# silelis_version1.net
KiCad netlist of a schematic drawn in EAGLE
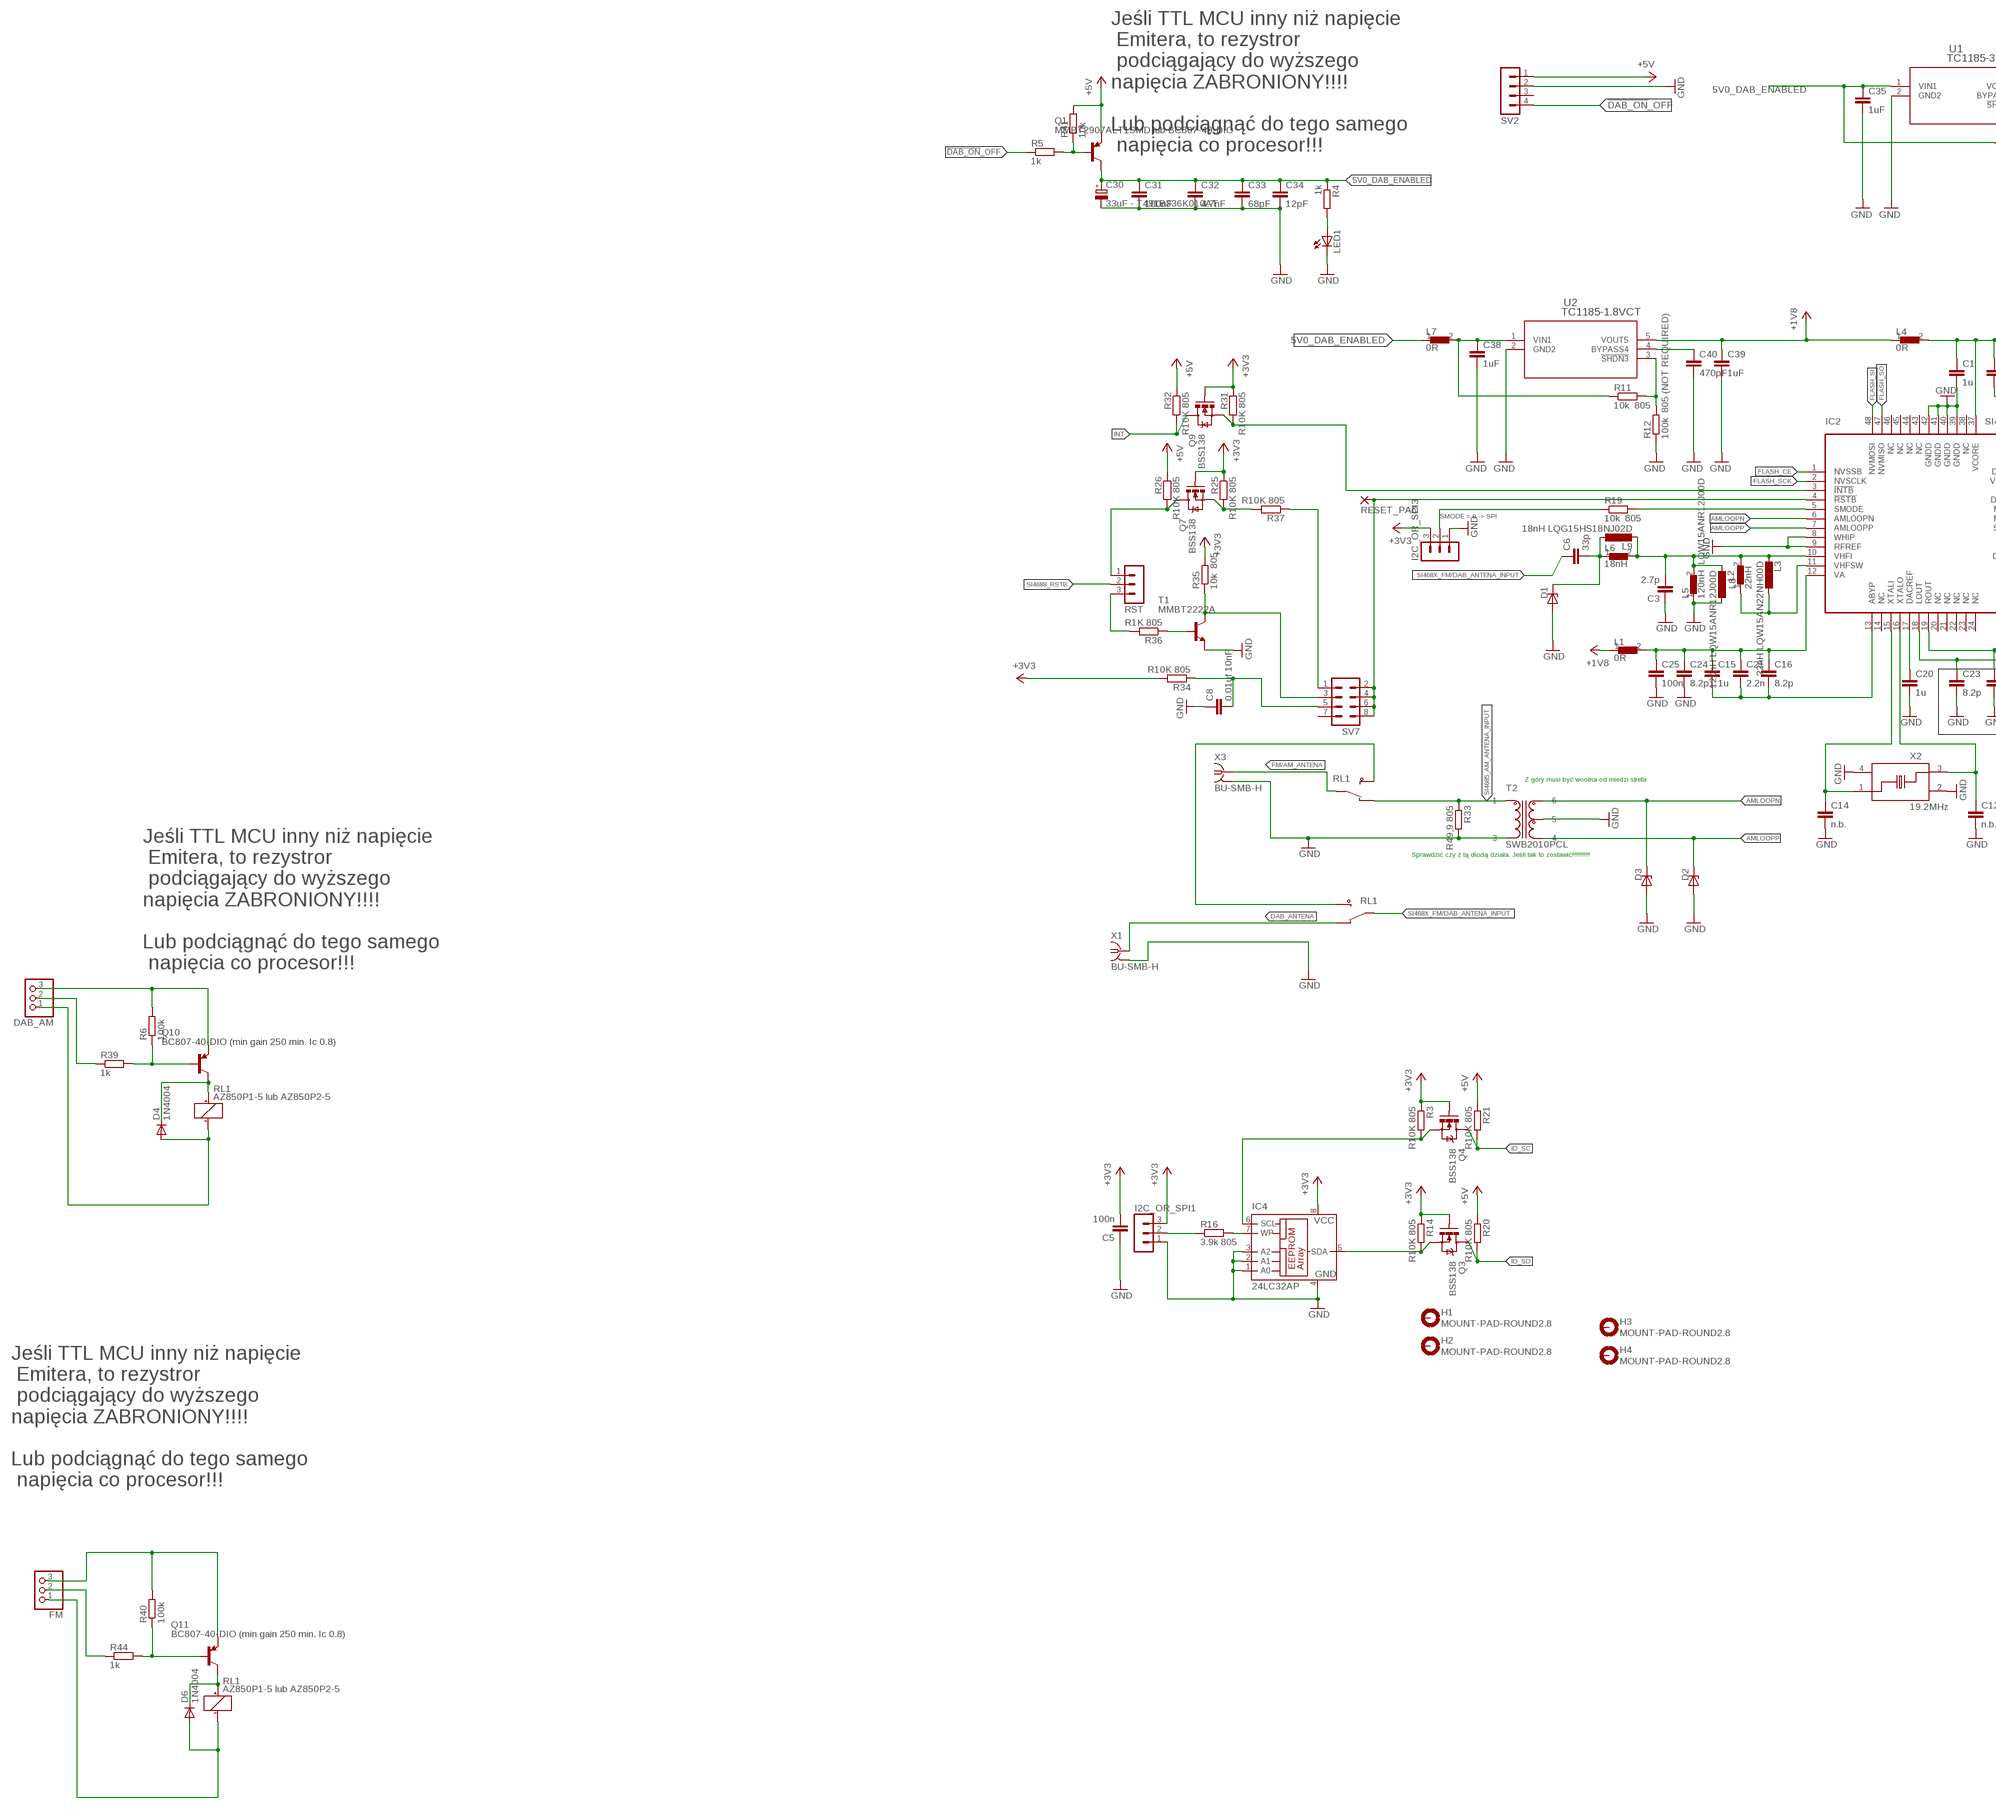
[diagram p0: schematic, sheet 1, part 1 of 2]
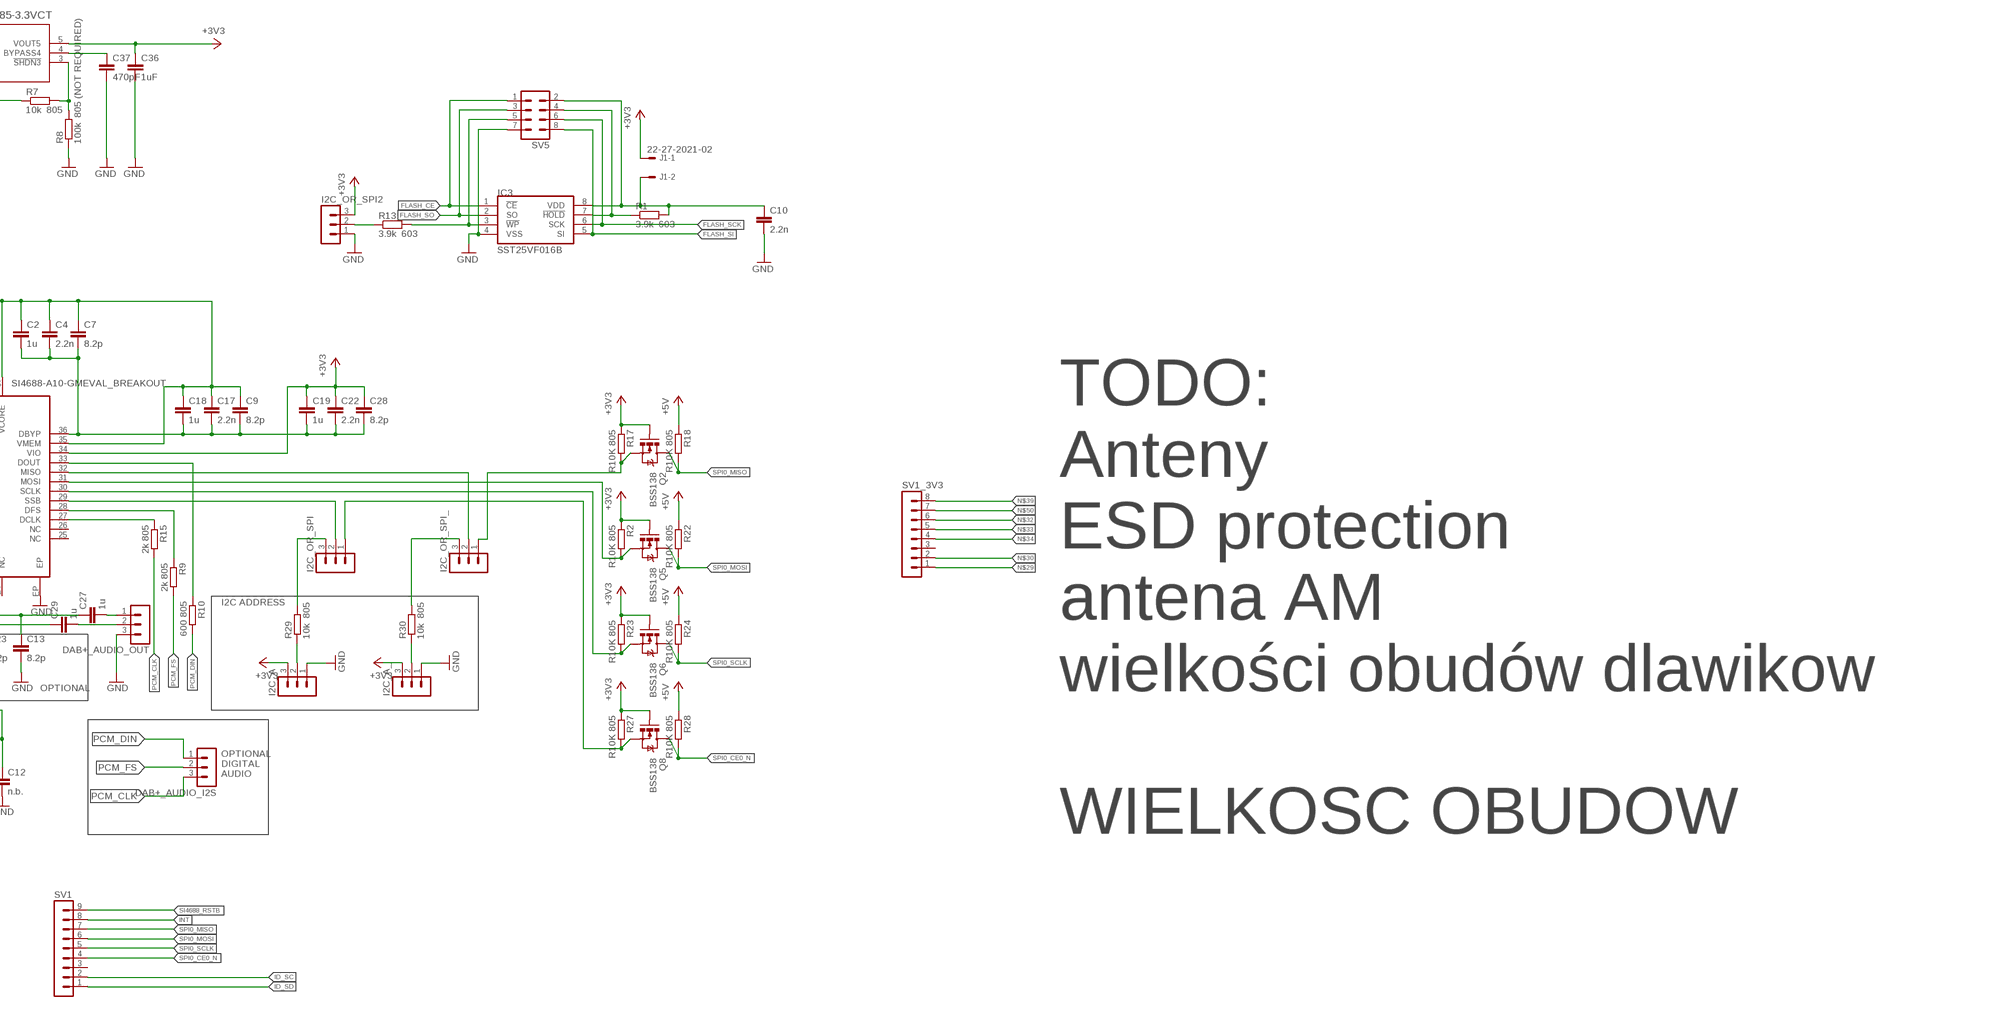
[diagram p1: schematic, sheet 1, part 2 of 2]

(export (version "E")
  (design (tool "Eeschema 10.0.6"))
  (components
    (comp (ref "C1")
      (value "1u")
      (footprint "eagle-import:C0805")
      (libsource (lib "eagle-import") (part "resistor_C-EUC0805"))
    )
    (comp (ref "C2")
      (value "1u")
      (footprint "eagle-import:C0805")
      (libsource (lib "eagle-import") (part "resistor_C-EUC0805"))
    )
    (comp (ref "C3")
      (value "2.7p")
      (footprint "eagle-import:C0603")
      (libsource (lib "eagle-import") (part "resistor_C-EUC0603"))
    )
    (comp (ref "C4")
      (value "2.2n")
      (footprint "eagle-import:C0805")
      (libsource (lib "eagle-import") (part "resistor_C-EUC0805"))
    )
    (comp (ref "C5")
      (value "100n")
      (footprint "eagle-import:C0805")
      (libsource (lib "eagle-import") (part "resistor_C-EUC0805"))
    )
    (comp (ref "C6")
      (value "33p")
      (footprint "eagle-import:C0603")
      (libsource (lib "eagle-import") (part "resistor_C-EUC0603"))
    )
    (comp (ref "C7")
      (value "8.2p")
      (footprint "eagle-import:C0805")
      (libsource (lib "eagle-import") (part "resistor_C-EUC0805"))
    )
    (comp (ref "C8")
      (value "0.01uf 10nF")
      (footprint "eagle-import:C0805")
      (libsource (lib "eagle-import") (part "C-EUC0805"))
    )
    (comp (ref "C9")
      (value "8.2p")
      (footprint "eagle-import:C0805")
      (libsource (lib "eagle-import") (part "resistor_C-EUC0805"))
    )
    (comp (ref "C10")
      (value "2.2n")
      (footprint "eagle-import:C0805")
      (libsource (lib "eagle-import") (part "resistor_C-EUC0805"))
    )
    (comp (ref "C12")
      (value "n.b.")
      (footprint "eagle-import:C0805")
      (libsource (lib "eagle-import") (part "resistor_C-EUC0805"))
    )
    (comp (ref "C13")
      (value "8.2p")
      (footprint "eagle-import:C0805")
      (libsource (lib "eagle-import") (part "resistor_C-EUC0805"))
    )
    (comp (ref "C14")
      (value "n.b.")
      (footprint "eagle-import:C0805")
      (libsource (lib "eagle-import") (part "resistor_C-EUC0805"))
    )
    (comp (ref "C15")
      (value "1u")
      (footprint "eagle-import:C0805")
      (libsource (lib "eagle-import") (part "resistor_C-EUC0805"))
    )
    (comp (ref "C16")
      (value "8.2p")
      (footprint "eagle-import:C0805")
      (libsource (lib "eagle-import") (part "resistor_C-EUC0805"))
    )
    (comp (ref "C17")
      (value "2.2n")
      (footprint "eagle-import:C0805")
      (libsource (lib "eagle-import") (part "resistor_C-EUC0805"))
    )
    (comp (ref "C18")
      (value "1u")
      (footprint "eagle-import:C0805")
      (libsource (lib "eagle-import") (part "resistor_C-EUC0805"))
    )
    (comp (ref "C19")
      (value "1u")
      (footprint "eagle-import:C0805")
      (libsource (lib "eagle-import") (part "resistor_C-EUC0805"))
    )
    (comp (ref "C20")
      (value "1u")
      (footprint "eagle-import:C0805")
      (libsource (lib "eagle-import") (part "resistor_C-EUC0805"))
    )
    (comp (ref "C21")
      (value "2.2n")
      (footprint "eagle-import:C0805")
      (libsource (lib "eagle-import") (part "resistor_C-EUC0805"))
    )
    (comp (ref "C22")
      (value "2.2n")
      (footprint "eagle-import:C0805")
      (libsource (lib "eagle-import") (part "resistor_C-EUC0805"))
    )
    (comp (ref "C23")
      (value "8.2p")
      (footprint "eagle-import:C0805")
      (libsource (lib "eagle-import") (part "resistor_C-EUC0805"))
    )
    (comp (ref "C24")
      (value "8.2p")
      (footprint "eagle-import:C0805")
      (libsource (lib "eagle-import") (part "resistor_C-EUC0805"))
    )
    (comp (ref "C25")
      (value "100n")
      (footprint "eagle-import:C0805")
      (libsource (lib "eagle-import") (part "resistor_C-EUC0805"))
    )
    (comp (ref "C27")
      (value "1u")
      (footprint "eagle-import:C0805")
      (libsource (lib "eagle-import") (part "resistor_C-EUC0805"))
    )
    (comp (ref "C28")
      (value "8.2p")
      (footprint "eagle-import:C0805")
      (libsource (lib "eagle-import") (part "resistor_C-EUC0805"))
    )
    (comp (ref "C29")
      (value "1u")
      (footprint "eagle-import:C0805")
      (libsource (lib "eagle-import") (part "resistor_C-EUC0805"))
    )
    (comp (ref "C30")
      (value "33uF - T491B336K010AT")
      (footprint "eagle-import:SMC_B")
      (fields (field (name "PARTNUM") "TAJB336K010R") (field (name "SUPPLIER") "TME"))
      (libsource (lib "eagle-import") (part "CPOL-EUSMCB"))
    )
    (comp (ref "C31")
      (value "100nF")
      (footprint "eagle-import:C0805")
      (libsource (lib "eagle-import") (part "resistor_C-EUC0805"))
    )
    (comp (ref "C32")
      (value "4.7nF")
      (footprint "eagle-import:C0805")
      (libsource (lib "eagle-import") (part "resistor_C-EUC0805"))
    )
    (comp (ref "C33")
      (value "68pF")
      (footprint "eagle-import:C0805")
      (libsource (lib "eagle-import") (part "resistor_C-EUC0805"))
    )
    (comp (ref "C34")
      (value "12pF")
      (footprint "eagle-import:C0603K")
      (libsource (lib "eagle-import") (part "resistor_C-EUC0603K"))
    )
    (comp (ref "C35")
      (value "1uF")
      (footprint "eagle-import:C0805")
      (libsource (lib "eagle-import") (part "resistor_C-EUC0805"))
    )
    (comp (ref "C36")
      (value "1uF")
      (footprint "eagle-import:C0805")
      (libsource (lib "eagle-import") (part "resistor_C-EUC0805"))
    )
    (comp (ref "C37")
      (value "470pF")
      (footprint "eagle-import:C0805")
      (libsource (lib "eagle-import") (part "resistor_C-EUC0805"))
    )
    (comp (ref "C38")
      (value "1uF")
      (footprint "eagle-import:C0805")
      (libsource (lib "eagle-import") (part "resistor_C-EUC0805"))
    )
    (comp (ref "C39")
      (value "1uF")
      (footprint "eagle-import:C0805")
      (libsource (lib "eagle-import") (part "resistor_C-EUC0805"))
    )
    (comp (ref "C40")
      (value "470pF")
      (footprint "eagle-import:C0805")
      (libsource (lib "eagle-import") (part "resistor_C-EUC0805"))
    )
    (comp (ref "D1")
      (value "ESD9L5.0")
      (footprint "eagle-import:SOD923")
      (libsource (lib "eagle-import") (part "ESD9L5.0"))
    )
    (comp (ref "D2")
      (value "ESD9L5.0")
      (footprint "eagle-import:SOD923")
      (libsource (lib "eagle-import") (part "ESD9L5.0"))
    )
    (comp (ref "D3")
      (value "ESD9L5.0")
      (footprint "eagle-import:SOD923")
      (libsource (lib "eagle-import") (part "ESD9L5.0"))
    )
    (comp (ref "D4")
      (value "1N4004")
      (footprint "eagle-import:DO41-10")
      (libsource (lib "eagle-import") (part "1N4004"))
    )
    (comp (ref "D6")
      (value "1N4004")
      (footprint "eagle-import:DO41-10")
      (libsource (lib "eagle-import") (part "1N4004"))
    )
    (comp (ref "DAB+_AUDIO_I2S")
      (value "MA03-1")
      (footprint "eagle-import:MA03-1")
      (libsource (lib "eagle-import") (part "MA03-1"))
    )
    (comp (ref "DAB+_AUDIO_OUT")
      (value "MA03-1")
      (footprint "eagle-import:MA03-1")
      (libsource (lib "eagle-import") (part "MA03-1"))
    )
    (comp (ref "DAB_AM")
      (value "PINHD-1X03_2.54-SMD")
      (footprint "eagle-import:1X03SMD")
      (libsource (lib "eagle-import") (part "PINHD-1X03_2.54-SMD"))
    )
    (comp (ref "FM")
      (value "PINHD-1X03_2.54-SMD")
      (footprint "eagle-import:1X03SMD")
      (libsource (lib "eagle-import") (part "PINHD-1X03_2.54-SMD"))
    )
    (comp (ref "H1")
      (value "MOUNT-PAD-ROUND2.8")
      (footprint "eagle-import:2,8-PAD")
      (libsource (lib "eagle-import") (part "MOUNT-PAD-ROUND2.8"))
    )
    (comp (ref "H2")
      (value "MOUNT-PAD-ROUND2.8")
      (footprint "eagle-import:2,8-PAD")
      (libsource (lib "eagle-import") (part "MOUNT-PAD-ROUND2.8"))
    )
    (comp (ref "H3")
      (value "MOUNT-PAD-ROUND2.8")
      (footprint "eagle-import:2,8-PAD")
      (libsource (lib "eagle-import") (part "MOUNT-PAD-ROUND2.8"))
    )
    (comp (ref "H4")
      (value "MOUNT-PAD-ROUND2.8")
      (footprint "eagle-import:2,8-PAD")
      (libsource (lib "eagle-import") (part "MOUNT-PAD-ROUND2.8"))
    )
    (comp (ref "I2C_A")
      (value "MA03-1")
      (footprint "eagle-import:MA03-1")
      (libsource (lib "eagle-import") (part "MA03-1"))
    )
    (comp (ref "I2C_A_")
      (value "MA03-1")
      (footprint "eagle-import:MA03-1")
      (libsource (lib "eagle-import") (part "MA03-1"))
    )
    (comp (ref "I2C_OR_SPI")
      (value "MA03-1")
      (footprint "eagle-import:MA03-1")
      (libsource (lib "eagle-import") (part "MA03-1"))
    )
    (comp (ref "I2C_OR_SPI1")
      (value "MA03-1")
      (footprint "eagle-import:MA03-1")
      (libsource (lib "eagle-import") (part "MA03-1"))
    )
    (comp (ref "I2C_OR_SPI2")
      (value "MA03-1")
      (footprint "eagle-import:MA03-1")
      (libsource (lib "eagle-import") (part "MA03-1"))
    )
    (comp (ref "I2C_OR_SPI3")
      (value "MA03-1")
      (footprint "eagle-import:MA03-1")
      (libsource (lib "eagle-import") (part "MA03-1"))
    )
    (comp (ref "I2C_OR_SPI_")
      (value "MA03-1")
      (footprint "eagle-import:MA03-1")
      (libsource (lib "eagle-import") (part "MA03-1"))
    )
    (comp (ref "IC2")
      (value "SI4688-A10-GMEVAL_BREAKOUT")
      (footprint "eagle-import:QFN48-BREAKOUT")
      (libsource (lib "eagle-import") (part "SI4688-A10-GMEVAL_BREAKOUT"))
    )
    (comp (ref "IC3")
      (value "SST25VF016B")
      (footprint "eagle-import:SOIC-8")
      (libsource (lib "eagle-import") (part "SST25VF016B"))
    )
    (comp (ref "IC4")
      (value "24LC32AP")
      (footprint "eagle-import:DIL8")
      (fields (field (name "MF") "MICROCHIP") (field (name "MPN") "24LC32A/P"))
      (libsource (lib "eagle-import") (part "24PLC32A"))
    )
    (comp (ref "J1")
      (value "22-27-2021-02")
      (footprint "eagle-import:6410-02")
      (libsource (lib "eagle-import") (part "22-?-0227-2021"))
    )
    (comp (ref "L1")
      (value "0R")
      (footprint "eagle-import:R0805")
      (libsource (lib "eagle-import") (part "FERRITR0805"))
    )
    (comp (ref "L2")
      (value "120nH LQW15ANR12J00D")
      (footprint "eagle-import:SMD0402")
      (libsource (lib "eagle-import") (part "L0402"))
    )
    (comp (ref "L3")
      (value "22nH LQW15AN22NH00D")
      (footprint "eagle-import:SMD0402")
      (libsource (lib "eagle-import") (part "L0402"))
    )
    (comp (ref "L4")
      (value "0R")
      (footprint "eagle-import:R0805")
      (libsource (lib "eagle-import") (part "FERRITR0805"))
    )
    (comp (ref "L5")
      (value "120nH LQW15ANR12J00D")
      (footprint "eagle-import:R0805")
      (libsource (lib "eagle-import") (part "FERRITR0805"))
    )
    (comp (ref "L6")
      (value "18nH")
      (footprint "eagle-import:R0805")
      (libsource (lib "eagle-import") (part "FERRITR0805"))
    )
    (comp (ref "L7")
      (value "0R")
      (footprint "eagle-import:R0805")
      (libsource (lib "eagle-import") (part "FERRITR0805"))
    )
    (comp (ref "L8")
      (value "22nH")
      (footprint "eagle-import:R0805")
      (libsource (lib "eagle-import") (part "FERRITR0805"))
    )
    (comp (ref "L9")
      (value "18nH LQG15HS18NJ02D")
      (footprint "eagle-import:SMD0402")
      (libsource (lib "eagle-import") (part "L0402"))
    )
    (comp (ref "LED1")
      (value "LED3MM")
      (footprint "eagle-import:LED3MM")
      (libsource (lib "eagle-import") (part "LED3MM"))
    )
    (comp (ref "Q1")
      (value "MMBT2907ALT1SMD lub BC807-40-DIO")
      (footprint "eagle-import:SOT23-BEC")
      (libsource (lib "eagle-import") (part "MMBT2907SMDALT1"))
    )
    (comp (ref "Q2")
      (value "BSS138")
      (footprint "eagle-import:SOT23-3")
      (libsource (lib "eagle-import") (part "MOSFET-NCHANNELSMD"))
    )
    (comp (ref "Q3")
      (value "BSS138")
      (footprint "eagle-import:SOT23-3")
      (libsource (lib "eagle-import") (part "MOSFET-NCHANNELSMD"))
    )
    (comp (ref "Q4")
      (value "BSS138")
      (footprint "eagle-import:SOT23-3")
      (libsource (lib "eagle-import") (part "MOSFET-NCHANNELSMD"))
    )
    (comp (ref "Q5")
      (value "BSS138")
      (footprint "eagle-import:SOT23-3")
      (libsource (lib "eagle-import") (part "MOSFET-NCHANNELSMD"))
    )
    (comp (ref "Q6")
      (value "BSS138")
      (footprint "eagle-import:SOT23-3")
      (libsource (lib "eagle-import") (part "MOSFET-NCHANNELSMD"))
    )
    (comp (ref "Q7")
      (value "BSS138")
      (footprint "eagle-import:SOT23-3")
      (libsource (lib "eagle-import") (part "MOSFET-NCHANNELSMD"))
    )
    (comp (ref "Q8")
      (value "BSS138")
      (footprint "eagle-import:SOT23-3")
      (libsource (lib "eagle-import") (part "MOSFET-NCHANNELSMD"))
    )
    (comp (ref "Q9")
      (value "BSS138")
      (footprint "eagle-import:SOT23-3")
      (libsource (lib "eagle-import") (part "MOSFET-NCHANNELSMD"))
    )
    (comp (ref "Q10")
      (value "BC807-40-DIO (min gain 250 min. Ic 0.8)")
      (footprint "eagle-import:SOT23-BEC")
      (libsource (lib "eagle-import") (part "MMBT2907SMDALT1"))
    )
    (comp (ref "Q11")
      (value "BC807-40-DIO (min gain 250 min. Ic 0.8)")
      (footprint "eagle-import:SOT23-BEC")
      (libsource (lib "eagle-import") (part "MMBT2907SMDALT1"))
    )
    (comp (ref "R1")
      (value "3.9k 603")
      (footprint "eagle-import:R0603")
      (libsource (lib "eagle-import") (part "R-EU_R0603"))
    )
    (comp (ref "R2")
      (value "R10K 805")
      (footprint "eagle-import:R0805")
      (libsource (lib "eagle-import") (part "R-EU_R0805"))
    )
    (comp (ref "R3")
      (value "R10K 805")
      (footprint "eagle-import:R0805")
      (libsource (lib "eagle-import") (part "R-EU_R0805"))
    )
    (comp (ref "R4")
      (value "1k")
      (footprint "eagle-import:M0805")
      (libsource (lib "eagle-import") (part "R-EU_M0805"))
    )
    (comp (ref "R5")
      (value "1k")
      (footprint "eagle-import:M0805")
      (libsource (lib "eagle-import") (part "R-EU_M0805"))
    )
    (comp (ref "R6")
      (value "100k")
      (footprint "eagle-import:M0805")
      (libsource (lib "eagle-import") (part "R-EU_M0805"))
    )
    (comp (ref "R7")
      (value "10k 805")
      (footprint "eagle-import:M0805")
      (libsource (lib "eagle-import") (part "R-EU_M0805"))
    )
    (comp (ref "R8")
      (value "100k 805 (NOT REQUIRED)")
      (footprint "eagle-import:M0805")
      (libsource (lib "eagle-import") (part "R-EU_M0805"))
    )
    (comp (ref "R9")
      (value "2k 805")
      (footprint "eagle-import:M0805")
      (libsource (lib "eagle-import") (part "R-EU_M0805"))
    )
    (comp (ref "R10")
      (value "600 805")
      (footprint "eagle-import:M0805")
      (libsource (lib "eagle-import") (part "R-EU_M0805"))
    )
    (comp (ref "R11")
      (value "10k 805")
      (footprint "eagle-import:M0805")
      (libsource (lib "eagle-import") (part "R-EU_M0805"))
    )
    (comp (ref "R12")
      (value "100k 805 (NOT REQUIRED)")
      (footprint "eagle-import:M0805")
      (libsource (lib "eagle-import") (part "R-EU_M0805"))
    )
    (comp (ref "R13")
      (value "3.9k 603")
      (footprint "eagle-import:R0603")
      (libsource (lib "eagle-import") (part "R-EU_R0603"))
    )
    (comp (ref "R14")
      (value "R10K 805")
      (footprint "eagle-import:R0805")
      (libsource (lib "eagle-import") (part "R-EU_R0805"))
    )
    (comp (ref "R15")
      (value "2k 805")
      (footprint "eagle-import:M0805")
      (libsource (lib "eagle-import") (part "R-EU_M0805"))
    )
    (comp (ref "R16")
      (value "3.9k 805")
      (footprint "eagle-import:R0805")
      (libsource (lib "eagle-import") (part "R-EU_R0805"))
    )
    (comp (ref "R17")
      (value "R10K 805")
      (footprint "eagle-import:R0805")
      (libsource (lib "eagle-import") (part "R-EU_R0805"))
    )
    (comp (ref "R18")
      (value "R10K 805")
      (footprint "eagle-import:R0805")
      (libsource (lib "eagle-import") (part "R-EU_R0805"))
    )
    (comp (ref "R19")
      (value "10k 805")
      (footprint "eagle-import:M0805")
      (libsource (lib "eagle-import") (part "R-EU_M0805"))
    )
    (comp (ref "R20")
      (value "R10K 805")
      (footprint "eagle-import:R0805")
      (libsource (lib "eagle-import") (part "R-EU_R0805"))
    )
    (comp (ref "R21")
      (value "R10K 805")
      (footprint "eagle-import:R0805")
      (libsource (lib "eagle-import") (part "R-EU_R0805"))
    )
    (comp (ref "R22")
      (value "R10K 805")
      (footprint "eagle-import:R0805")
      (libsource (lib "eagle-import") (part "R-EU_R0805"))
    )
    (comp (ref "R23")
      (value "R10K 805")
      (footprint "eagle-import:R0805")
      (libsource (lib "eagle-import") (part "R-EU_R0805"))
    )
    (comp (ref "R24")
      (value "R10K 805")
      (footprint "eagle-import:R0805")
      (libsource (lib "eagle-import") (part "R-EU_R0805"))
    )
    (comp (ref "R25")
      (value "R10K 805")
      (footprint "eagle-import:R0805")
      (libsource (lib "eagle-import") (part "R-EU_R0805"))
    )
    (comp (ref "R26")
      (value "R10K 805")
      (footprint "eagle-import:R0805")
      (libsource (lib "eagle-import") (part "R-EU_R0805"))
    )
    (comp (ref "R27")
      (value "R10K 805")
      (footprint "eagle-import:R0805")
      (libsource (lib "eagle-import") (part "R-EU_R0805"))
    )
    (comp (ref "R28")
      (value "R10K 805")
      (footprint "eagle-import:R0805")
      (libsource (lib "eagle-import") (part "R-EU_R0805"))
    )
    (comp (ref "R29")
      (value "10k 805")
      (footprint "eagle-import:M0805")
      (libsource (lib "eagle-import") (part "R-EU_M0805"))
    )
    (comp (ref "R30")
      (value "10k 805")
      (footprint "eagle-import:M0805")
      (libsource (lib "eagle-import") (part "R-EU_M0805"))
    )
    (comp (ref "R31")
      (value "R10K 805")
      (footprint "eagle-import:R0805")
      (libsource (lib "eagle-import") (part "R-EU_R0805"))
    )
    (comp (ref "R32")
      (value "R10K 805")
      (footprint "eagle-import:R0805")
      (libsource (lib "eagle-import") (part "R-EU_R0805"))
    )
    (comp (ref "R33")
      (value "R49,9 805")
      (footprint "eagle-import:R0805")
      (libsource (lib "eagle-import") (part "resistor_R-EU_R0805"))
    )
    (comp (ref "R34")
      (value "R10K 805")
      (footprint "eagle-import:R0805")
      (libsource (lib "eagle-import") (part "resistor_R-EU_R0805"))
    )
    (comp (ref "R35")
      (value "10k 805")
      (footprint "eagle-import:M0805")
      (libsource (lib "eagle-import") (part "R-EU_M0805"))
    )
    (comp (ref "R36")
      (value "R1K 805")
      (footprint "eagle-import:R0805")
      (libsource (lib "eagle-import") (part "resistor_R-EU_R0805"))
    )
    (comp (ref "R37")
      (value "R10K 805")
      (footprint "eagle-import:R0805")
      (libsource (lib "eagle-import") (part "resistor_R-EU_R0805"))
    )
    (comp (ref "R39")
      (value "1k")
      (footprint "eagle-import:M0805")
      (libsource (lib "eagle-import") (part "R-EU_M0805"))
    )
    (comp (ref "R40")
      (value "100k")
      (footprint "eagle-import:M0805")
      (libsource (lib "eagle-import") (part "R-EU_M0805"))
    )
    (comp (ref "R41")
      (value "10k")
      (footprint "eagle-import:M0805")
      (libsource (lib "eagle-import") (part "R-EU_M0805"))
    )
    (comp (ref "R44")
      (value "1k")
      (footprint "eagle-import:M0805")
      (libsource (lib "eagle-import") (part "R-EU_M0805"))
    )
    (comp (ref "RESET_PAD")
      (value "SMD2")
      (footprint "eagle-import:SMD1,27-2,54")
      (libsource (lib "eagle-import") (part "SMD2"))
    )
    (comp (ref "RL1")
      (value "AZ850P1-5 lub AZ850P2-5")
      (footprint "eagle-import:AZ850-2C")
      (libsource (lib "eagle-import") (part "AZ850P2-12"))
    )
    (comp (ref "RST")
      (value "MA03-1")
      (footprint "eagle-import:MA03-1")
      (libsource (lib "eagle-import") (part "MA03-1"))
    )
    (comp (ref "SV1")
      (value "MA09-1")
      (footprint "eagle-import:MA09-1")
      (libsource (lib "eagle-import") (part "MA09-1"))
    )
    (comp (ref "SV1_3V3")
      (value "MA08-1")
      (footprint "eagle-import:MA08-1")
      (libsource (lib "eagle-import") (part "MA08-1"))
    )
    (comp (ref "SV2")
      (value "MA04-1")
      (footprint "eagle-import:MA04-1")
      (libsource (lib "eagle-import") (part "MA04-1"))
    )
    (comp (ref "SV5")
      (value "MA04-2")
      (footprint "eagle-import:MA04-2")
      (libsource (lib "eagle-import") (part "MA04-2"))
    )
    (comp (ref "SV7")
      (value "MA04-2")
      (footprint "eagle-import:MA04-2")
      (libsource (lib "eagle-import") (part "MA04-2"))
    )
    (comp (ref "T1")
      (value "MMBT2222A")
      (footprint "eagle-import:SOT23-BEC")
      (libsource (lib "eagle-import") (part "-NPN-SOT23-BECMMBT918LT1"))
    )
    (comp (ref "T2")
      (value "SWB2010PCL")
      (footprint "eagle-import:COILCRAFT-SWBXXXX-PCL")
      (libsource (lib "eagle-import") (part "SWB2010PCL"))
    )
    (comp (ref "U1")
      (value "TC1185-3.3VCT")
      (footprint "eagle-import:SOT-23-5_MC-M")
      (fields (field (name "MANUFACTURER_PART_NUMBER") "TC1185X.XXCT713"))
      (libsource (lib "eagle-import") (part "TC1185-X.XXCT713SOT-23-5_MC-M"))
    )
    (comp (ref "U2")
      (value "TC1185-1.8VCT")
      (footprint "eagle-import:SOT-23-5_MC-M")
      (fields (field (name "MANUFACTURER_PART_NUMBER") "TC1185X.XXCT713"))
      (libsource (lib "eagle-import") (part "TC1185-X.XXCT713SOT-23-5_MC-M"))
    )
    (comp (ref "X1")
      (value "BU-SMB-H")
      (footprint "eagle-import:BU-SMB-H")
      (libsource (lib "eagle-import") (part "BU-SMB-H"))
    )
    (comp (ref "X2")
      (value "19.2MHz")
      (footprint "eagle-import:XTAL_3.2X2.5")
      (libsource (lib "eagle-import") (part "XTAL_3.2X2.5"))
    )
    (comp (ref "X3")
      (value "BU-SMB-H")
      (footprint "eagle-import:BU-SMB-H")
      (libsource (lib "eagle-import") (part "BU-SMB-H"))
    )
  )
  (nets
    (net (code "1") (name "+1V8") (class "Default")
      (node (ref "C39") (pin "1") (pinfunction "1_1") (pintype "passive"))
      (node (ref "L1") (pin "1") (pinfunction "1_1") (pintype "passive"))
      (node (ref "L4") (pin "1") (pinfunction "1_1") (pintype "passive"))
      (node (ref "U2") (pin "5") (pinfunction "VOUT5_5") (pintype "passive"))
    )
    (net (code "2") (name "+3V3") (class "Default")
      (node (ref "C19") (pin "1") (pinfunction "1_1") (pintype "passive"))
      (node (ref "C22") (pin "1") (pinfunction "1_1") (pintype "passive"))
      (node (ref "C28") (pin "1") (pinfunction "1_1") (pintype "passive"))
      (node (ref "C36") (pin "1") (pinfunction "1_1") (pintype "passive"))
      (node (ref "C5") (pin "2") (pinfunction "2_2") (pintype "passive"))
      (node (ref "I2C_A") (pin "3") (pinfunction "3_3") (pintype "passive"))
      (node (ref "I2C_A_") (pin "3") (pinfunction "3_3") (pintype "passive"))
      (node (ref "I2C_OR_SPI1") (pin "3") (pinfunction "3_3") (pintype "passive"))
      (node (ref "I2C_OR_SPI2") (pin "3") (pinfunction "3_3") (pintype "passive"))
      (node (ref "I2C_OR_SPI3") (pin "3") (pinfunction "3_3") (pintype "passive"))
      (node (ref "IC2") (pin "34") (pinfunction "VIO_34") (pintype "power_in"))
      (node (ref "IC4") (pin "8") (pinfunction "VCC_8") (pintype "power_in"))
      (node (ref "J1") (pin "1") (pinfunction "S_1") (pintype "passive"))
      (node (ref "Q2") (pin "1") (pinfunction "G_1") (pintype "passive"))
      (node (ref "Q3") (pin "1") (pinfunction "G_1") (pintype "passive"))
      (node (ref "Q4") (pin "1") (pinfunction "G_1") (pintype "passive"))
      (node (ref "Q5") (pin "1") (pinfunction "G_1") (pintype "passive"))
      (node (ref "Q6") (pin "1") (pinfunction "G_1") (pintype "passive"))
      (node (ref "Q7") (pin "1") (pinfunction "G_1") (pintype "passive"))
      (node (ref "Q8") (pin "1") (pinfunction "G_1") (pintype "passive"))
      (node (ref "Q9") (pin "1") (pinfunction "G_1") (pintype "passive"))
      (node (ref "R14") (pin "1") (pinfunction "1_1") (pintype "passive"))
      (node (ref "R17") (pin "1") (pinfunction "1_1") (pintype "passive"))
      (node (ref "R2") (pin "1") (pinfunction "1_1") (pintype "passive"))
      (node (ref "R23") (pin "1") (pinfunction "1_1") (pintype "passive"))
      (node (ref "R25") (pin "1") (pinfunction "1_1") (pintype "passive"))
      (node (ref "R27") (pin "1") (pinfunction "1_1") (pintype "passive"))
      (node (ref "R3") (pin "1") (pinfunction "1_1") (pintype "passive"))
      (node (ref "R31") (pin "1") (pinfunction "1_1") (pintype "passive"))
      (node (ref "R34") (pin "2") (pinfunction "2_2") (pintype "passive"))
      (node (ref "R35") (pin "2") (pinfunction "2_2") (pintype "passive"))
      (node (ref "U1") (pin "5") (pinfunction "VOUT5_5") (pintype "passive"))
    )
    (net (code "3") (name "+5V") (class "Default")
      (node (ref "Q1") (pin "E") (pinfunction "E_E") (pintype "passive"))
      (node (ref "R18") (pin "1") (pinfunction "1_1") (pintype "passive"))
      (node (ref "R20") (pin "1") (pinfunction "1_1") (pintype "passive"))
      (node (ref "R21") (pin "1") (pinfunction "1_1") (pintype "passive"))
      (node (ref "R22") (pin "1") (pinfunction "1_1") (pintype "passive"))
      (node (ref "R24") (pin "1") (pinfunction "1_1") (pintype "passive"))
      (node (ref "R26") (pin "1") (pinfunction "1_1") (pintype "passive"))
      (node (ref "R28") (pin "1") (pinfunction "1_1") (pintype "passive"))
      (node (ref "R32") (pin "1") (pinfunction "1_1") (pintype "passive"))
      (node (ref "R41") (pin "2") (pinfunction "2_2") (pintype "passive"))
      (node (ref "SV2") (pin "1") (pinfunction "1_1") (pintype "passive"))
    )
    (net (code "4") (name "/~{DAB_ON}_OFF") (class "Default")
      (node (ref "R5") (pin "1") (pinfunction "1_1") (pintype "passive"))
      (node (ref "SV2") (pin "4") (pinfunction "4_4") (pintype "passive"))
    )
    (net (code "5") (name "5V0_DAB_ENABLED") (class "Default")
      (node (ref "C30") (pin "+") (pinfunction "+_+") (pintype "passive"))
      (node (ref "C31") (pin "1") (pinfunction "1_1") (pintype "passive"))
      (node (ref "C32") (pin "1") (pinfunction "1_1") (pintype "passive"))
      (node (ref "C33") (pin "1") (pinfunction "1_1") (pintype "passive"))
      (node (ref "C34") (pin "1") (pinfunction "1_1") (pintype "passive"))
      (node (ref "C35") (pin "1") (pinfunction "1_1") (pintype "passive"))
      (node (ref "L7") (pin "1") (pinfunction "1_1") (pintype "passive"))
      (node (ref "Q1") (pin "C") (pinfunction "C_C") (pintype "passive"))
      (node (ref "R4") (pin "1") (pinfunction "1_1") (pintype "passive"))
      (node (ref "R7") (pin "1") (pinfunction "1_1") (pintype "passive"))
      (node (ref "U1") (pin "1") (pinfunction "VIN1_1") (pintype "passive"))
    )
    (net (code "6") (name "AMLOOPN") (class "Default")
      (node (ref "D3") (pin "K") (pinfunction "C_K") (pintype "passive"))
      (node (ref "IC2") (pin "6") (pinfunction "AMLOOPN_6") (pintype "power_in"))
      (node (ref "T2") (pin "P$6") (pinfunction "6_P$6") (pintype "bidirectional"))
    )
    (net (code "7") (name "AMLOOPP") (class "Default")
      (node (ref "D2") (pin "K") (pinfunction "C_K") (pintype "passive"))
      (node (ref "IC2") (pin "7") (pinfunction "AMLOOPP_7") (pintype "power_in"))
      (node (ref "T2") (pin "P$4") (pinfunction "4_P$4") (pintype "bidirectional"))
    )
    (net (code "8") (name "DAB_ANTENA") (class "Default")
      (node (ref "RL1") (pin "P$9") (pinfunction "4_P$9") (pintype "passive"))
      (node (ref "X1") (pin "1") (pinfunction "1_1") (pintype "passive"))
    )
    (net (code "9") (name "FLASH_CE") (class "Default")
      (node (ref "IC2") (pin "1") (pinfunction "NVSSB_1") (pintype "output"))
      (node (ref "IC3") (pin "1") (pinfunction "~{CE}_1") (pintype "input"))
      (node (ref "SV5") (pin "1") (pinfunction "1_1") (pintype "passive"))
    )
    (net (code "10") (name "FLASH_SCK") (class "Default")
      (node (ref "IC2") (pin "2") (pinfunction "NVSCLK_2") (pintype "output"))
      (node (ref "IC3") (pin "6") (pinfunction "SCK_6") (pintype "input"))
      (node (ref "SV5") (pin "6") (pinfunction "6_6") (pintype "passive"))
    )
    (net (code "11") (name "FLASH_SI") (class "Default")
      (node (ref "IC2") (pin "48") (pinfunction "NVMOSI_48") (pintype "output"))
      (node (ref "IC3") (pin "5") (pinfunction "SI_5") (pintype "input"))
      (node (ref "SV5") (pin "8") (pinfunction "8_8") (pintype "passive"))
    )
    (net (code "12") (name "FLASH_SO") (class "Default")
      (node (ref "IC2") (pin "47") (pinfunction "NVMISO_47") (pintype "input"))
      (node (ref "IC3") (pin "2") (pinfunction "SO_2") (pintype "output"))
      (node (ref "SV5") (pin "3") (pinfunction "3_3") (pintype "passive"))
    )
    (net (code "13") (name "FM{slash}AM_ANTENA") (class "Default")
      (node (ref "RL1") (pin "P$3") (pinfunction "5_P$3") (pintype "passive"))
      (node (ref "X3") (pin "1") (pinfunction "1_1") (pintype "passive"))
    )
    (net (code "14") (name "GND") (class "Default")
      (node (ref "C1") (pin "2") (pinfunction "2_2") (pintype "passive"))
      (node (ref "C10") (pin "2") (pinfunction "2_2") (pintype "passive"))
      (node (ref "C12") (pin "2") (pinfunction "2_2") (pintype "passive"))
      (node (ref "C13") (pin "2") (pinfunction "2_2") (pintype "passive"))
      (node (ref "C14") (pin "2") (pinfunction "2_2") (pintype "passive"))
      (node (ref "C20") (pin "2") (pinfunction "2_2") (pintype "passive"))
      (node (ref "C23") (pin "2") (pinfunction "2_2") (pintype "passive"))
      (node (ref "C24") (pin "2") (pinfunction "2_2") (pintype "passive"))
      (node (ref "C25") (pin "2") (pinfunction "2_2") (pintype "passive"))
      (node (ref "C3") (pin "1") (pinfunction "1_1") (pintype "passive"))
      (node (ref "C30") (pin "-") (pinfunction "-_-") (pintype "passive"))
      (node (ref "C31") (pin "2") (pinfunction "2_2") (pintype "passive"))
      (node (ref "C32") (pin "2") (pinfunction "2_2") (pintype "passive"))
      (node (ref "C33") (pin "2") (pinfunction "2_2") (pintype "passive"))
      (node (ref "C34") (pin "2") (pinfunction "2_2") (pintype "passive"))
      (node (ref "C35") (pin "2") (pinfunction "2_2") (pintype "passive"))
      (node (ref "C36") (pin "2") (pinfunction "2_2") (pintype "passive"))
      (node (ref "C37") (pin "2") (pinfunction "2_2") (pintype "passive"))
      (node (ref "C38") (pin "2") (pinfunction "2_2") (pintype "passive"))
      (node (ref "C39") (pin "2") (pinfunction "2_2") (pintype "passive"))
      (node (ref "C40") (pin "2") (pinfunction "2_2") (pintype "passive"))
      (node (ref "C5") (pin "1") (pinfunction "1_1") (pintype "passive"))
      (node (ref "C8") (pin "1") (pinfunction "1_1") (pintype "passive"))
      (node (ref "D1") (pin "A") (pinfunction "A_A") (pintype "passive"))
      (node (ref "D2") (pin "A") (pinfunction "A_A") (pintype "passive"))
      (node (ref "D3") (pin "A") (pinfunction "A_A") (pintype "passive"))
      (node (ref "DAB+_AUDIO_OUT") (pin "3") (pinfunction "3_3") (pintype "passive"))
      (node (ref "I2C_A") (pin "1") (pinfunction "1_1") (pintype "passive"))
      (node (ref "I2C_A_") (pin "1") (pinfunction "1_1") (pintype "passive"))
      (node (ref "I2C_OR_SPI1") (pin "1") (pinfunction "1_1") (pintype "passive"))
      (node (ref "I2C_OR_SPI2") (pin "1") (pinfunction "1_1") (pintype "passive"))
      (node (ref "I2C_OR_SPI3") (pin "1") (pinfunction "1_1") (pintype "passive"))
      (node (ref "IC2") (pin "39") (pinfunction "GNDD_39") (pintype "power_in"))
      (node (ref "IC2") (pin "40") (pinfunction "GNDD_40") (pintype "power_in"))
      (node (ref "IC2") (pin "41") (pinfunction "GNDD_41") (pintype "power_in"))
      (node (ref "IC2") (pin "42") (pinfunction "GNDD_42") (pintype "power_in"))
      (node (ref "IC2") (pin "8") (pinfunction "WHIP_8") (pintype "power_in"))
      (node (ref "IC2") (pin "9") (pinfunction "RFREF_9") (pintype "power_in"))
      (node (ref "IC2") (pin "EP") (pinfunction "EP_EP") (pintype "bidirectional"))
      (node (ref "IC3") (pin "4") (pinfunction "VSS_4") (pintype "power_in"))
      (node (ref "IC4") (pin "1") (pinfunction "A0_1") (pintype "input"))
      (node (ref "IC4") (pin "2") (pinfunction "A1_2") (pintype "input"))
      (node (ref "IC4") (pin "3") (pinfunction "A2_3") (pintype "input"))
      (node (ref "IC4") (pin "4") (pinfunction "GND_4") (pintype "power_in"))
      (node (ref "L2") (pin "1") (pinfunction "1_1") (pintype "passive"))
      (node (ref "L5") (pin "1") (pinfunction "1_1") (pintype "passive"))
      (node (ref "LED1") (pin "K") (pinfunction "C_K") (pintype "passive"))
      (node (ref "R12") (pin "1") (pinfunction "1_1") (pintype "passive"))
      (node (ref "R33") (pin "2") (pinfunction "2_2") (pintype "passive"))
      (node (ref "R8") (pin "1") (pinfunction "1_1") (pintype "passive"))
      (node (ref "SV2") (pin "2") (pinfunction "2_2") (pintype "passive"))
      (node (ref "SV5") (pin "7") (pinfunction "7_7") (pintype "passive"))
      (node (ref "T1") (pin "E") (pinfunction "E_E") (pintype "passive"))
      (node (ref "T2") (pin "P$3") (pinfunction "3_P$3") (pintype "bidirectional"))
      (node (ref "T2") (pin "P$5") (pinfunction "5_P$5") (pintype "bidirectional"))
      (node (ref "U1") (pin "2") (pinfunction "GND2_2") (pintype "passive"))
      (node (ref "U2") (pin "2") (pinfunction "GND2_2") (pintype "passive"))
      (node (ref "X1") (pin "2") (pinfunction "2_2") (pintype "passive"))
      (node (ref "X1") (pin "3") (pinfunction "2_3") (pintype "passive"))
      (node (ref "X1") (pin "4") (pinfunction "2_4") (pintype "passive"))
      (node (ref "X1") (pin "5") (pinfunction "2_5") (pintype "passive"))
      (node (ref "X2") (pin "2") (pinfunction "GND_2") (pintype "power_in"))
      (node (ref "X2") (pin "4") (pinfunction "GND_4") (pintype "power_in"))
      (node (ref "X3") (pin "2") (pinfunction "2_2") (pintype "passive"))
      (node (ref "X3") (pin "3") (pinfunction "2_3") (pintype "passive"))
      (node (ref "X3") (pin "4") (pinfunction "2_4") (pintype "passive"))
      (node (ref "X3") (pin "5") (pinfunction "2_5") (pintype "passive"))
    )
    (net (code "15") (name "ID_SC") (class "Default")
      (node (ref "Q4") (pin "3") (pinfunction "D_3") (pintype "passive"))
      (node (ref "R21") (pin "2") (pinfunction "2_2") (pintype "passive"))
      (node (ref "SV1") (pin "2") (pinfunction "2_2") (pintype "passive"))
    )
    (net (code "16") (name "ID_SD") (class "Default")
      (node (ref "Q3") (pin "3") (pinfunction "D_3") (pintype "passive"))
      (node (ref "R20") (pin "2") (pinfunction "2_2") (pintype "passive"))
      (node (ref "SV1") (pin "1") (pinfunction "1_1") (pintype "passive"))
    )
    (net (code "17") (name "INT") (class "Default")
      (node (ref "Q9") (pin "3") (pinfunction "D_3") (pintype "passive"))
      (node (ref "R32") (pin "2") (pinfunction "2_2") (pintype "passive"))
      (node (ref "SV1") (pin "8") (pinfunction "8_8") (pintype "passive"))
    )
    (net (code "18") (name "N$29") (class "Default")
      (node (ref "IC4") (pin "5") (pinfunction "SDA_5") (pintype "bidirectional"))
      (node (ref "Q3") (pin "2") (pinfunction "S_2") (pintype "passive"))
      (node (ref "R14") (pin "2") (pinfunction "2_2") (pintype "passive"))
      (node (ref "SV1_3V3") (pin "1") (pinfunction "1_1") (pintype "passive"))
    )
    (net (code "19") (name "N$30") (class "Default")
      (node (ref "IC4") (pin "6") (pinfunction "SCL_6") (pintype "input"))
      (node (ref "Q4") (pin "2") (pinfunction "S_2") (pintype "passive"))
      (node (ref "R3") (pin "2") (pinfunction "2_2") (pintype "passive"))
      (node (ref "SV1_3V3") (pin "2") (pinfunction "2_2") (pintype "passive"))
    )
    (net (code "20") (name "N$32") (class "Default")
      (node (ref "IC2") (pin "31") (pinfunction "MOSI_31") (pintype "bidirectional"))
      (node (ref "Q5") (pin "2") (pinfunction "S_2") (pintype "passive"))
      (node (ref "R2") (pin "2") (pinfunction "2_2") (pintype "passive"))
      (node (ref "SV1_3V3") (pin "6") (pinfunction "6_6") (pintype "passive"))
    )
    (net (code "21") (name "N$33") (class "Default")
      (node (ref "IC2") (pin "30") (pinfunction "SCLK_30") (pintype "input"))
      (node (ref "Q6") (pin "2") (pinfunction "S_2") (pintype "passive"))
      (node (ref "R23") (pin "2") (pinfunction "2_2") (pintype "passive"))
      (node (ref "SV1_3V3") (pin "5") (pinfunction "5_5") (pintype "passive"))
    )
    (net (code "22") (name "N$34") (class "Default")
      (node (ref "I2C_OR_SPI") (pin "1") (pinfunction "1_1") (pintype "passive"))
      (node (ref "Q8") (pin "2") (pinfunction "S_2") (pintype "passive"))
      (node (ref "R27") (pin "2") (pinfunction "2_2") (pintype "passive"))
      (node (ref "SV1_3V3") (pin "4") (pinfunction "4_4") (pintype "passive"))
    )
    (net (code "23") (name "N$39") (class "Default")
      (node (ref "IC2") (pin "3") (pinfunction "~{INTB}_3") (pintype "output"))
      (node (ref "Q9") (pin "2") (pinfunction "S_2") (pintype "passive"))
      (node (ref "R31") (pin "2") (pinfunction "2_2") (pintype "passive"))
      (node (ref "SV1_3V3") (pin "8") (pinfunction "8_8") (pintype "passive"))
    )
    (net (code "24") (name "N$50") (class "Default")
      (node (ref "I2C_OR_SPI_") (pin "1") (pinfunction "1_1") (pintype "passive"))
      (node (ref "Q2") (pin "2") (pinfunction "S_2") (pintype "passive"))
      (node (ref "R17") (pin "2") (pinfunction "2_2") (pintype "passive"))
      (node (ref "SV1_3V3") (pin "7") (pinfunction "7_7") (pintype "passive"))
    )
    (net (code "25") (name "Net-(C8-Pad2)") (class "Default")
      (node (ref "C8") (pin "2") (pinfunction "2_2") (pintype "passive"))
      (node (ref "R34") (pin "1") (pinfunction "1_1") (pintype "passive"))
      (node (ref "SV7") (pin "5") (pinfunction "5_5") (pintype "passive"))
    )
    (net (code "26") (name "Net-(C27-Pad2)") (class "Default")
      (node (ref "C27") (pin "2") (pinfunction "2_2") (pintype "passive"))
      (node (ref "DAB+_AUDIO_OUT") (pin "1") (pinfunction "1_1") (pintype "passive"))
    )
    (net (code "27") (name "Net-(C29-Pad2)") (class "Default")
      (node (ref "C29") (pin "2") (pinfunction "2_2") (pintype "passive"))
      (node (ref "DAB+_AUDIO_OUT") (pin "2") (pinfunction "2_2") (pintype "passive"))
    )
    (net (code "28") (name "Net-(D1-C)") (class "Default")
      (node (ref "C6") (pin "2") (pinfunction "2_2") (pintype "passive"))
      (node (ref "D1") (pin "K") (pinfunction "C_K") (pintype "passive"))
      (node (ref "L6") (pin "1") (pinfunction "1_1") (pintype "passive"))
      (node (ref "L9") (pin "1") (pinfunction "1_1") (pintype "passive"))
    )
    (net (code "29") (name "Net-(DAB_AM-Pad2)") (class "Default")
      (node (ref "DAB_AM") (pin "2") (pinfunction "2_2") (pintype "passive"))
      (node (ref "R39") (pin "1") (pinfunction "1_1") (pintype "passive"))
    )
    (net (code "30") (name "Net-(DAB_AM-Pad3)") (class "Default")
      (node (ref "DAB_AM") (pin "3") (pinfunction "3_3") (pintype "passive"))
      (node (ref "Q10") (pin "E") (pinfunction "E_E") (pintype "passive"))
      (node (ref "R6") (pin "2") (pinfunction "2_2") (pintype "passive"))
    )
    (net (code "31") (name "Net-(FM-Pad2)") (class "Default")
      (node (ref "FM") (pin "2") (pinfunction "2_2") (pintype "passive"))
      (node (ref "R44") (pin "1") (pinfunction "1_1") (pintype "passive"))
    )
    (net (code "32") (name "Net-(FM-Pad3)") (class "Default")
      (node (ref "FM") (pin "3") (pinfunction "3_3") (pintype "passive"))
      (node (ref "Q11") (pin "E") (pinfunction "E_E") (pintype "passive"))
      (node (ref "R40") (pin "2") (pinfunction "2_2") (pintype "passive"))
    )
    (net (code "33") (name "Net-(I2C_A-Pad2)") (class "Default")
      (node (ref "I2C_A") (pin "2") (pinfunction "2_2") (pintype "passive"))
      (node (ref "R29") (pin "1") (pinfunction "1_1") (pintype "passive"))
    )
    (net (code "34") (name "Net-(I2C_A_-Pad2)") (class "Default")
      (node (ref "I2C_A_") (pin "2") (pinfunction "2_2") (pintype "passive"))
      (node (ref "R30") (pin "1") (pinfunction "1_1") (pintype "passive"))
    )
    (net (code "35") (name "Net-(I2C_OR_SPI-Pad3)") (class "Default")
      (node (ref "I2C_OR_SPI") (pin "3") (pinfunction "3_3") (pintype "passive"))
      (node (ref "R29") (pin "2") (pinfunction "2_2") (pintype "passive"))
    )
    (net (code "36") (name "Net-(I2C_OR_SPI1-Pad2)") (class "Default")
      (node (ref "I2C_OR_SPI1") (pin "2") (pinfunction "2_2") (pintype "passive"))
      (node (ref "R16") (pin "1") (pinfunction "1_1") (pintype "passive"))
    )
    (net (code "37") (name "Net-(I2C_OR_SPI2-Pad2)") (class "Default")
      (node (ref "I2C_OR_SPI2") (pin "2") (pinfunction "2_2") (pintype "passive"))
      (node (ref "R13") (pin "1") (pinfunction "1_1") (pintype "passive"))
    )
    (net (code "38") (name "Net-(I2C_OR_SPI3-Pad2)") (class "Default")
      (node (ref "I2C_OR_SPI3") (pin "2") (pinfunction "2_2") (pintype "passive"))
      (node (ref "R19") (pin "1") (pinfunction "1_1") (pintype "passive"))
    )
    (net (code "39") (name "Net-(I2C_OR_SPI_-Pad3)") (class "Default")
      (node (ref "I2C_OR_SPI_") (pin "3") (pinfunction "3_3") (pintype "passive"))
      (node (ref "R30") (pin "2") (pinfunction "2_2") (pintype "passive"))
    )
    (net (code "40") (name "Net-(IC2-ABYP)") (class "Default")
      (node (ref "C15") (pin "2") (pinfunction "2_2") (pintype "passive"))
      (node (ref "C16") (pin "2") (pinfunction "2_2") (pintype "passive"))
      (node (ref "C21") (pin "2") (pinfunction "2_2") (pintype "passive"))
      (node (ref "IC2") (pin "13") (pinfunction "ABYP_13") (pintype "power_in"))
    )
    (net (code "41") (name "Net-(IC2-DACREF)") (class "Default")
      (node (ref "C20") (pin "1") (pinfunction "1_1") (pintype "passive"))
      (node (ref "IC2") (pin "17") (pinfunction "DACREF_17") (pintype "power_in"))
    )
    (net (code "42") (name "Net-(IC2-DBYP)") (class "Default")
      (node (ref "C17") (pin "2") (pinfunction "2_2") (pintype "passive"))
      (node (ref "C18") (pin "2") (pinfunction "2_2") (pintype "passive"))
      (node (ref "C19") (pin "2") (pinfunction "2_2") (pintype "passive"))
      (node (ref "C2") (pin "2") (pinfunction "2_2") (pintype "passive"))
      (node (ref "C22") (pin "2") (pinfunction "2_2") (pintype "passive"))
      (node (ref "C28") (pin "2") (pinfunction "2_2") (pintype "passive"))
      (node (ref "C4") (pin "2") (pinfunction "2_2") (pintype "passive"))
      (node (ref "C7") (pin "2") (pinfunction "2_2") (pintype "passive"))
      (node (ref "C9") (pin "2") (pinfunction "2_2") (pintype "passive"))
      (node (ref "IC2") (pin "36") (pinfunction "DBYP_36") (pintype "power_in"))
    )
    (net (code "43") (name "Net-(IC2-DCLK)") (class "Default")
      (node (ref "IC2") (pin "27") (pinfunction "DCLK_27") (pintype "bidirectional"))
      (node (ref "R15") (pin "1") (pinfunction "1_1") (pintype "passive"))
    )
    (net (code "44") (name "Net-(IC2-DFS)") (class "Default")
      (node (ref "IC2") (pin "28") (pinfunction "DFS_28") (pintype "bidirectional"))
      (node (ref "R9") (pin "1") (pinfunction "1_1") (pintype "passive"))
    )
    (net (code "45") (name "Net-(IC2-DOUT)") (class "Default")
      (node (ref "IC2") (pin "33") (pinfunction "DOUT_33") (pintype "output"))
      (node (ref "R10") (pin "1") (pinfunction "1_1") (pintype "passive"))
    )
    (net (code "46") (name "Net-(IC2-LOUT)") (class "Default")
      (node (ref "C23") (pin "1") (pinfunction "1_1") (pintype "passive"))
      (node (ref "C29") (pin "1") (pinfunction "1_1") (pintype "passive"))
      (node (ref "IC2") (pin "18") (pinfunction "LOUT_18") (pintype "output"))
    )
    (net (code "47") (name "Net-(IC2-MISO)") (class "Default")
      (node (ref "I2C_OR_SPI_") (pin "2") (pinfunction "2_2") (pintype "passive"))
      (node (ref "IC2") (pin "32") (pinfunction "MISO_32") (pintype "bidirectional"))
    )
    (net (code "48") (name "Net-(IC2-ROUT)") (class "Default")
      (node (ref "C13") (pin "1") (pinfunction "1_1") (pintype "passive"))
      (node (ref "C27") (pin "1") (pinfunction "1_1") (pintype "passive"))
      (node (ref "IC2") (pin "19") (pinfunction "ROUT_19") (pintype "output"))
    )
    (net (code "49") (name "Net-(IC2-SMODE)") (class "Default")
      (node (ref "IC2") (pin "5") (pinfunction "SMODE_5") (pintype "input"))
      (node (ref "R19") (pin "2") (pinfunction "2_2") (pintype "passive"))
    )
    (net (code "50") (name "Net-(IC2-SSB)") (class "Default")
      (node (ref "I2C_OR_SPI") (pin "2") (pinfunction "2_2") (pintype "passive"))
      (node (ref "IC2") (pin "29") (pinfunction "SSB_29") (pintype "input"))
    )
    (net (code "51") (name "Net-(IC2-VA)") (class "Default")
      (node (ref "C15") (pin "1") (pinfunction "1_1") (pintype "passive"))
      (node (ref "C16") (pin "1") (pinfunction "1_1") (pintype "passive"))
      (node (ref "C21") (pin "1") (pinfunction "1_1") (pintype "passive"))
      (node (ref "C24") (pin "1") (pinfunction "1_1") (pintype "passive"))
      (node (ref "C25") (pin "1") (pinfunction "1_1") (pintype "passive"))
      (node (ref "IC2") (pin "12") (pinfunction "VA_12") (pintype "power_in"))
      (node (ref "L1") (pin "2") (pinfunction "2_2") (pintype "passive"))
    )
    (net (code "52") (name "Net-(IC2-VCORE)") (class "Default")
      (node (ref "C1") (pin "1") (pinfunction "1_1") (pintype "passive"))
      (node (ref "C17") (pin "1") (pinfunction "1_1") (pintype "passive"))
      (node (ref "C18") (pin "1") (pinfunction "1_1") (pintype "passive"))
      (node (ref "C2") (pin "1") (pinfunction "1_1") (pintype "passive"))
      (node (ref "C4") (pin "1") (pinfunction "1_1") (pintype "passive"))
      (node (ref "C7") (pin "1") (pinfunction "1_1") (pintype "passive"))
      (node (ref "C9") (pin "1") (pinfunction "1_1") (pintype "passive"))
      (node (ref "IC2") (pin "35") (pinfunction "VMEM_35") (pintype "power_in"))
      (node (ref "IC2") (pin "37") (pinfunction "VCORE_37") (pintype "power_in"))
      (node (ref "L4") (pin "2") (pinfunction "2_2") (pintype "passive"))
    )
    (net (code "53") (name "Net-(IC2-VHFI)") (class "Default")
      (node (ref "C3") (pin "2") (pinfunction "2_2") (pintype "passive"))
      (node (ref "IC2") (pin "10") (pinfunction "VHFI_10") (pintype "input"))
      (node (ref "L2") (pin "2") (pinfunction "2_2") (pintype "passive"))
      (node (ref "L3") (pin "2") (pinfunction "2_2") (pintype "passive"))
      (node (ref "L5") (pin "2") (pinfunction "2_2") (pintype "passive"))
      (node (ref "L6") (pin "2") (pinfunction "2_2") (pintype "passive"))
      (node (ref "L8") (pin "2") (pinfunction "2_2") (pintype "passive"))
      (node (ref "L9") (pin "2") (pinfunction "2_2") (pintype "passive"))
    )
    (net (code "54") (name "Net-(IC2-VHFSW)") (class "Default")
      (node (ref "IC2") (pin "11") (pinfunction "VHFSW_11") (pintype "output"))
      (node (ref "L3") (pin "1") (pinfunction "1_1") (pintype "passive"))
      (node (ref "L8") (pin "1") (pinfunction "1_1") (pintype "passive"))
    )
    (net (code "55") (name "Net-(IC2-XTALI)") (class "Default")
      (node (ref "C14") (pin "1") (pinfunction "1_1") (pintype "passive"))
      (node (ref "IC2") (pin "15") (pinfunction "XTALI_15") (pintype "input"))
      (node (ref "X2") (pin "1") (pinfunction "1_1") (pintype "passive"))
    )
    (net (code "56") (name "Net-(IC2-XTALO)") (class "Default")
      (node (ref "C12") (pin "1") (pinfunction "1_1") (pintype "passive"))
      (node (ref "IC2") (pin "16") (pinfunction "XTALO_16") (pintype "output"))
      (node (ref "X2") (pin "3") (pinfunction "3_3") (pintype "passive"))
    )
    (net (code "57") (name "Net-(IC2-~{RSTB})") (class "Default")
      (node (ref "IC2") (pin "4") (pinfunction "~{RSTB}_4") (pintype "input"))
      (node (ref "RESET_PAD") (pin "1") (pinfunction "P_1") (pintype "passive"))
      (node (ref "SV7") (pin "2") (pinfunction "2_2") (pintype "passive"))
      (node (ref "SV7") (pin "4") (pinfunction "4_4") (pintype "passive"))
      (node (ref "SV7") (pin "6") (pinfunction "6_6") (pintype "passive"))
      (node (ref "SV7") (pin "8") (pinfunction "8_8") (pintype "passive"))
    )
    (net (code "58") (name "Net-(IC3-VDD)") (class "Default")
      (node (ref "C10") (pin "1") (pinfunction "1_1") (pintype "passive"))
      (node (ref "IC3") (pin "8") (pinfunction "VDD_8") (pintype "power_in"))
      (node (ref "J1") (pin "2") (pinfunction "S_2") (pintype "passive"))
      (node (ref "R1") (pin "2") (pinfunction "2_2") (pintype "passive"))
      (node (ref "SV5") (pin "2") (pinfunction "2_2") (pintype "passive"))
    )
    (net (code "59") (name "Net-(IC3-~{HOLD})") (class "Default")
      (node (ref "IC3") (pin "7") (pinfunction "~{HOLD}_7") (pintype "input"))
      (node (ref "R1") (pin "1") (pinfunction "1_1") (pintype "passive"))
      (node (ref "SV5") (pin "4") (pinfunction "4_4") (pintype "passive"))
    )
    (net (code "60") (name "Net-(IC3-~{WP})") (class "Default")
      (node (ref "IC3") (pin "3") (pinfunction "~{WP}_3") (pintype "input"))
      (node (ref "R13") (pin "2") (pinfunction "2_2") (pintype "passive"))
      (node (ref "SV5") (pin "5") (pinfunction "5_5") (pintype "passive"))
    )
    (net (code "61") (name "Net-(IC4-WP)") (class "Default")
      (node (ref "IC4") (pin "7") (pinfunction "WP_7") (pintype "input"))
      (node (ref "R16") (pin "2") (pinfunction "2_2") (pintype "passive"))
    )
    (net (code "62") (name "Net-(LED1-PadA)") (class "Default")
      (node (ref "LED1") (pin "A") (pinfunction "A_A") (pintype "passive"))
      (node (ref "R4") (pin "2") (pinfunction "2_2") (pintype "passive"))
    )
    (net (code "63") (name "Net-(Q1-PadB)") (class "Default")
      (node (ref "Q1") (pin "B") (pinfunction "B_B") (pintype "passive"))
      (node (ref "R41") (pin "1") (pinfunction "1_1") (pintype "passive"))
      (node (ref "R5") (pin "2") (pinfunction "2_2") (pintype "passive"))
    )
    (net (code "64") (name "Net-(Q7-D)") (class "Default")
      (node (ref "Q7") (pin "3") (pinfunction "D_3") (pintype "passive"))
      (node (ref "R26") (pin "2") (pinfunction "2_2") (pintype "passive"))
      (node (ref "RST") (pin "1") (pinfunction "1_1") (pintype "passive"))
    )
    (net (code "65") (name "Net-(Q7-S)") (class "Default")
      (node (ref "Q7") (pin "2") (pinfunction "S_2") (pintype "passive"))
      (node (ref "R25") (pin "2") (pinfunction "2_2") (pintype "passive"))
      (node (ref "R37") (pin "2") (pinfunction "2_2") (pintype "passive"))
    )
    (net (code "66") (name "Net-(Q10-PadB)") (class "Default")
      (node (ref "Q10") (pin "B") (pinfunction "B_B") (pintype "passive"))
      (node (ref "R39") (pin "2") (pinfunction "2_2") (pintype "passive"))
      (node (ref "R6") (pin "1") (pinfunction "1_1") (pintype "passive"))
    )
    (net (code "67") (name "Net-(Q11-PadB)") (class "Default")
      (node (ref "Q11") (pin "B") (pinfunction "B_B") (pintype "passive"))
      (node (ref "R40") (pin "1") (pinfunction "1_1") (pintype "passive"))
      (node (ref "R44") (pin "2") (pinfunction "2_2") (pintype "passive"))
    )
    (net (code "68") (name "Net-(R35-Pad1)") (class "Default")
      (node (ref "R35") (pin "1") (pinfunction "1_1") (pintype "passive"))
      (node (ref "SV7") (pin "3") (pinfunction "3_3") (pintype "passive"))
      (node (ref "T1") (pin "C") (pinfunction "C_C") (pintype "passive"))
    )
    (net (code "69") (name "Net-(R36-Pad1)") (class "Default")
      (node (ref "R36") (pin "1") (pinfunction "1_1") (pintype "passive"))
      (node (ref "T1") (pin "B") (pinfunction "B_B") (pintype "passive"))
    )
    (net (code "70") (name "Net-(R36-Pad2)") (class "Default")
      (node (ref "R36") (pin "2") (pinfunction "2_2") (pintype "passive"))
      (node (ref "RST") (pin "3") (pinfunction "3_3") (pintype "passive"))
    )
    (net (code "71") (name "Net-(R37-Pad1)") (class "Default")
      (node (ref "R37") (pin "1") (pinfunction "1_1") (pintype "passive"))
      (node (ref "SV7") (pin "1") (pinfunction "1_1") (pintype "passive"))
    )
    (net (code "72") (name "Net-(RL1A-+)") (class "Default")
      (node (ref "D4") (pin "C") (pinfunction "C_C") (pintype "passive"))
      (node (ref "Q10") (pin "C") (pinfunction "C_C") (pintype "passive"))
      (node (ref "RL1") (pin "P$1") (pinfunction "+_P$1") (pintype "passive"))
    )
    (net (code "73") (name "Net-(RL1A--)") (class "Default")
      (node (ref "D4") (pin "A") (pinfunction "A_A") (pintype "passive"))
      (node (ref "DAB_AM") (pin "1") (pinfunction "1_1") (pintype "passive"))
      (node (ref "RL1") (pin "P$5") (pinfunction "-_P$5") (pintype "passive"))
    )
    (net (code "74") (name "Net-(RL1B-+)") (class "Default")
      (node (ref "D6") (pin "C") (pinfunction "C_C") (pintype "passive"))
      (node (ref "Q11") (pin "C") (pinfunction "C_C") (pintype "passive"))
      (node (ref "RL1") (pin "P$10") (pinfunction "+_P$10") (pintype "passive"))
    )
    (net (code "75") (name "Net-(RL1B--)") (class "Default")
      (node (ref "D6") (pin "A") (pinfunction "A_A") (pintype "passive"))
      (node (ref "FM") (pin "1") (pinfunction "1_1") (pintype "passive"))
      (node (ref "RL1") (pin "P$6") (pinfunction "-_P$6") (pintype "passive"))
    )
    (net (code "76") (name "Net-(RL1C-6)") (class "Default")
      (node (ref "RL1") (pin "P$4") (pinfunction "6_P$4") (pintype "passive"))
      (node (ref "RL1") (pin "P$7") (pinfunction "6_P$7") (pintype "passive"))
    )
    (net (code "77") (name "Net-(U1-BYPASS4)") (class "Default")
      (node (ref "C37") (pin "1") (pinfunction "1_1") (pintype "passive"))
      (node (ref "U1") (pin "4") (pinfunction "BYPASS4_4") (pintype "passive"))
    )
    (net (code "78") (name "Net-(U1-~{SHDN3})") (class "Default")
      (node (ref "R7") (pin "2") (pinfunction "2_2") (pintype "passive"))
      (node (ref "R8") (pin "2") (pinfunction "2_2") (pintype "passive"))
      (node (ref "U1") (pin "3") (pinfunction "~{SHDN3}_3") (pintype "passive"))
    )
    (net (code "79") (name "Net-(U2-BYPASS4)") (class "Default")
      (node (ref "C40") (pin "1") (pinfunction "1_1") (pintype "passive"))
      (node (ref "U2") (pin "4") (pinfunction "BYPASS4_4") (pintype "passive"))
    )
    (net (code "80") (name "Net-(U2-VIN1)") (class "Default")
      (node (ref "C38") (pin "1") (pinfunction "1_1") (pintype "passive"))
      (node (ref "L7") (pin "2") (pinfunction "2_2") (pintype "passive"))
      (node (ref "R11") (pin "1") (pinfunction "1_1") (pintype "passive"))
      (node (ref "U2") (pin "1") (pinfunction "VIN1_1") (pintype "passive"))
    )
    (net (code "81") (name "Net-(U2-~{SHDN3})") (class "Default")
      (node (ref "R11") (pin "2") (pinfunction "2_2") (pintype "passive"))
      (node (ref "R12") (pin "2") (pinfunction "2_2") (pintype "passive"))
      (node (ref "U2") (pin "3") (pinfunction "~{SHDN3}_3") (pintype "passive"))
    )
    (net (code "82") (name "PCM_CLK") (class "Default")
      (node (ref "DAB+_AUDIO_I2S") (pin "3") (pinfunction "3_3") (pintype "passive"))
      (node (ref "R15") (pin "2") (pinfunction "2_2") (pintype "passive"))
    )
    (net (code "83") (name "PCM_DIN") (class "Default")
      (node (ref "DAB+_AUDIO_I2S") (pin "1") (pinfunction "1_1") (pintype "passive"))
      (node (ref "R10") (pin "2") (pinfunction "2_2") (pintype "passive"))
    )
    (net (code "84") (name "PCM_FS") (class "Default")
      (node (ref "DAB+_AUDIO_I2S") (pin "2") (pinfunction "2_2") (pintype "passive"))
      (node (ref "R9") (pin "2") (pinfunction "2_2") (pintype "passive"))
    )
    (net (code "85") (name "SI468X_FM{slash}DAB_ANTENA_INPUT") (class "Default")
      (node (ref "C6") (pin "1") (pinfunction "1_1") (pintype "passive"))
      (node (ref "RL1") (pin "P$8") (pinfunction "5_P$8") (pintype "passive"))
    )
    (net (code "86") (name "SI4685_AM_ANTENA_INPUT") (class "Default")
      (node (ref "R33") (pin "1") (pinfunction "1_1") (pintype "passive"))
      (node (ref "RL1") (pin "P$2") (pinfunction "4_P$2") (pintype "passive"))
      (node (ref "T2") (pin "P$1") (pinfunction "1_P$1") (pintype "bidirectional"))
    )
    (net (code "87") (name "SI4688_RSTB") (class "Default")
      (node (ref "RST") (pin "2") (pinfunction "2_2") (pintype "passive"))
      (node (ref "SV1") (pin "9") (pinfunction "9_9") (pintype "passive"))
    )
    (net (code "88") (name "SPI0_CE0_N") (class "Default")
      (node (ref "Q8") (pin "3") (pinfunction "D_3") (pintype "passive"))
      (node (ref "R28") (pin "2") (pinfunction "2_2") (pintype "passive"))
      (node (ref "SV1") (pin "4") (pinfunction "4_4") (pintype "passive"))
    )
    (net (code "89") (name "SPI0_MISO") (class "Default")
      (node (ref "Q2") (pin "3") (pinfunction "D_3") (pintype "passive"))
      (node (ref "R18") (pin "2") (pinfunction "2_2") (pintype "passive"))
      (node (ref "SV1") (pin "7") (pinfunction "7_7") (pintype "passive"))
    )
    (net (code "90") (name "SPI0_MOSI") (class "Default")
      (node (ref "Q5") (pin "3") (pinfunction "D_3") (pintype "passive"))
      (node (ref "R22") (pin "2") (pinfunction "2_2") (pintype "passive"))
      (node (ref "SV1") (pin "6") (pinfunction "6_6") (pintype "passive"))
    )
    (net (code "91") (name "SPI0_SCLK") (class "Default")
      (node (ref "Q6") (pin "3") (pinfunction "D_3") (pintype "passive"))
      (node (ref "R24") (pin "2") (pinfunction "2_2") (pintype "passive"))
      (node (ref "SV1") (pin "5") (pinfunction "5_5") (pintype "passive"))
    )
    (net (code "92") (name "unconnected-(H1-MOUNT-PadB2,8)") (class "Default")
      (node (ref "H1") (pin "B2,8") (pinfunction "MOUNT_B2,8") (pintype "passive"))
    )
    (net (code "93") (name "unconnected-(H2-MOUNT-PadB2,8)") (class "Default")
      (node (ref "H2") (pin "B2,8") (pinfunction "MOUNT_B2,8") (pintype "passive"))
    )
    (net (code "94") (name "unconnected-(H3-MOUNT-PadB2,8)") (class "Default")
      (node (ref "H3") (pin "B2,8") (pinfunction "MOUNT_B2,8") (pintype "passive"))
    )
    (net (code "95") (name "unconnected-(H4-MOUNT-PadB2,8)") (class "Default")
      (node (ref "H4") (pin "B2,8") (pinfunction "MOUNT_B2,8") (pintype "passive"))
    )
    (net (code "96") (name "unconnected-(IC2-NC-Pad14)") (class "Default")
      (node (ref "IC2") (pin "14") (pinfunction "NC_14") (pintype "no_connect"))
    )
    (net (code "97") (name "unconnected-(IC2-NC-Pad20)") (class "Default")
      (node (ref "IC2") (pin "20") (pinfunction "NC_20") (pintype "no_connect"))
    )
    (net (code "98") (name "unconnected-(IC2-NC-Pad21)") (class "Default")
      (node (ref "IC2") (pin "21") (pinfunction "NC_21") (pintype "no_connect"))
    )
    (net (code "99") (name "unconnected-(IC2-NC-Pad22)") (class "Default")
      (node (ref "IC2") (pin "22") (pinfunction "NC_22") (pintype "no_connect"))
    )
    (net (code "100") (name "unconnected-(IC2-NC-Pad23)") (class "Default")
      (node (ref "IC2") (pin "23") (pinfunction "NC_23") (pintype "no_connect"))
    )
    (net (code "101") (name "unconnected-(IC2-NC-Pad24)") (class "Default")
      (node (ref "IC2") (pin "24") (pinfunction "NC_24") (pintype "no_connect"))
    )
    (net (code "102") (name "unconnected-(IC2-NC-Pad25)") (class "Default")
      (node (ref "IC2") (pin "25") (pinfunction "NC_25") (pintype "no_connect"))
    )
    (net (code "103") (name "unconnected-(IC2-NC-Pad26)") (class "Default")
      (node (ref "IC2") (pin "26") (pinfunction "NC_26") (pintype "no_connect"))
    )
    (net (code "104") (name "unconnected-(IC2-NC-Pad38)") (class "Default")
      (node (ref "IC2") (pin "38") (pinfunction "NC_38") (pintype "no_connect"))
    )
    (net (code "105") (name "unconnected-(IC2-NC-Pad43)") (class "Default")
      (node (ref "IC2") (pin "43") (pinfunction "NC_43") (pintype "no_connect"))
    )
    (net (code "106") (name "unconnected-(IC2-NC-Pad44)") (class "Default")
      (node (ref "IC2") (pin "44") (pinfunction "NC_44") (pintype "no_connect"))
    )
    (net (code "107") (name "unconnected-(IC2-NC-Pad45)") (class "Default")
      (node (ref "IC2") (pin "45") (pinfunction "NC_45") (pintype "no_connect"))
    )
    (net (code "108") (name "unconnected-(IC2-NC-Pad46)") (class "Default")
      (node (ref "IC2") (pin "46") (pinfunction "NC_46") (pintype "no_connect"))
    )
    (net (code "109") (name "unconnected-(SV1-Pad3)") (class "Default")
      (node (ref "SV1") (pin "3") (pinfunction "3_3") (pintype "passive"))
    )
    (net (code "110") (name "unconnected-(SV1_3V3-Pad3)") (class "Default")
      (node (ref "SV1_3V3") (pin "3") (pinfunction "3_3") (pintype "passive"))
    )
    (net (code "111") (name "unconnected-(SV2-Pad3)") (class "Default")
      (node (ref "SV2") (pin "3") (pinfunction "3_3") (pintype "passive"))
    )
    (net (code "112") (name "unconnected-(SV7-Pad7)") (class "Default")
      (node (ref "SV7") (pin "7") (pinfunction "7_7") (pintype "passive"))
    )
  )
)
